# parallel_R_buzzer_buttons.net
KiCad netlist of a schematic drawn in EAGLE
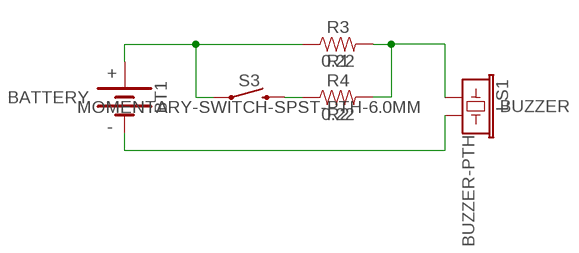
[diagram p0: schematic, sheet 1]

(export (version "E")
  (design (tool "Eeschema 10.0.6"))
  (components
    (comp (ref "BT1")
      (value "BATTERY-9V")
      (footprint "eagle-import:BATTCON_9V")
      (libsource (lib "eagle-import") (part "BATTERY-9V"))
    )
    (comp (ref "LS1")
      (value "BUZZER-PTH")
      (footprint "eagle-import:BUZZER-12MM")
      (libsource (lib "eagle-import") (part "BUZZER-PTH"))
    )
    (comp (ref "R3")
      (value "0.22")
      (footprint "eagle-import:0805")
      (libsource (lib "eagle-import") (part "0.22OHM-0805-1/4W-1%"))
    )
    (comp (ref "R4")
      (value "0.22")
      (footprint "eagle-import:0805")
      (libsource (lib "eagle-import") (part "0.22OHM-0805-1/4W-1%"))
    )
    (comp (ref "S3")
      (value "MOMENTARY-SWITCH-SPST-PTH-6.0MM")
      (footprint "eagle-import:TACTILE_SWITCH_PTH_6.0MM")
      (libsource (lib "eagle-import") (part "MOMENTARY-SWITCH-SPST-PTH-6.0MM"))
    )
  )
  (nets
    (net (code "1") (name "Net-(BT1-Pad+)") (class "Default")
      (node (ref "BT1") (pin "+") (pinfunction "+_+") (pintype "power_in"))
      (node (ref "R3") (pin "1") (pinfunction "1_1") (pintype "passive"))
      (node (ref "S3") (pin "1") (pinfunction "1_1") (pintype "passive"))
    )
    (net (code "2") (name "Net-(LS1-1)") (class "Default")
      (node (ref "LS1") (pin "+") (pinfunction "1_+") (pintype "passive"))
      (node (ref "R3") (pin "2") (pinfunction "2_2") (pintype "passive"))
      (node (ref "R4") (pin "2") (pinfunction "2_2") (pintype "passive"))
    )
    (net (code "3") (name "Net-(LS1-2)") (class "Default")
      (node (ref "BT1") (pin "-") (pinfunction "-_-") (pintype "power_in"))
      (node (ref "LS1") (pin "-") (pinfunction "2_-") (pintype "passive"))
    )
    (net (code "4") (name "Net-(S3-2)") (class "Default")
      (node (ref "R4") (pin "1") (pinfunction "1_1") (pintype "passive"))
      (node (ref "S3") (pin "3") (pinfunction "2_3") (pintype "passive"))
    )
  )
)
